# teensyMotors02_up_LED.net
KiCad netlist of a schematic drawn in EAGLE
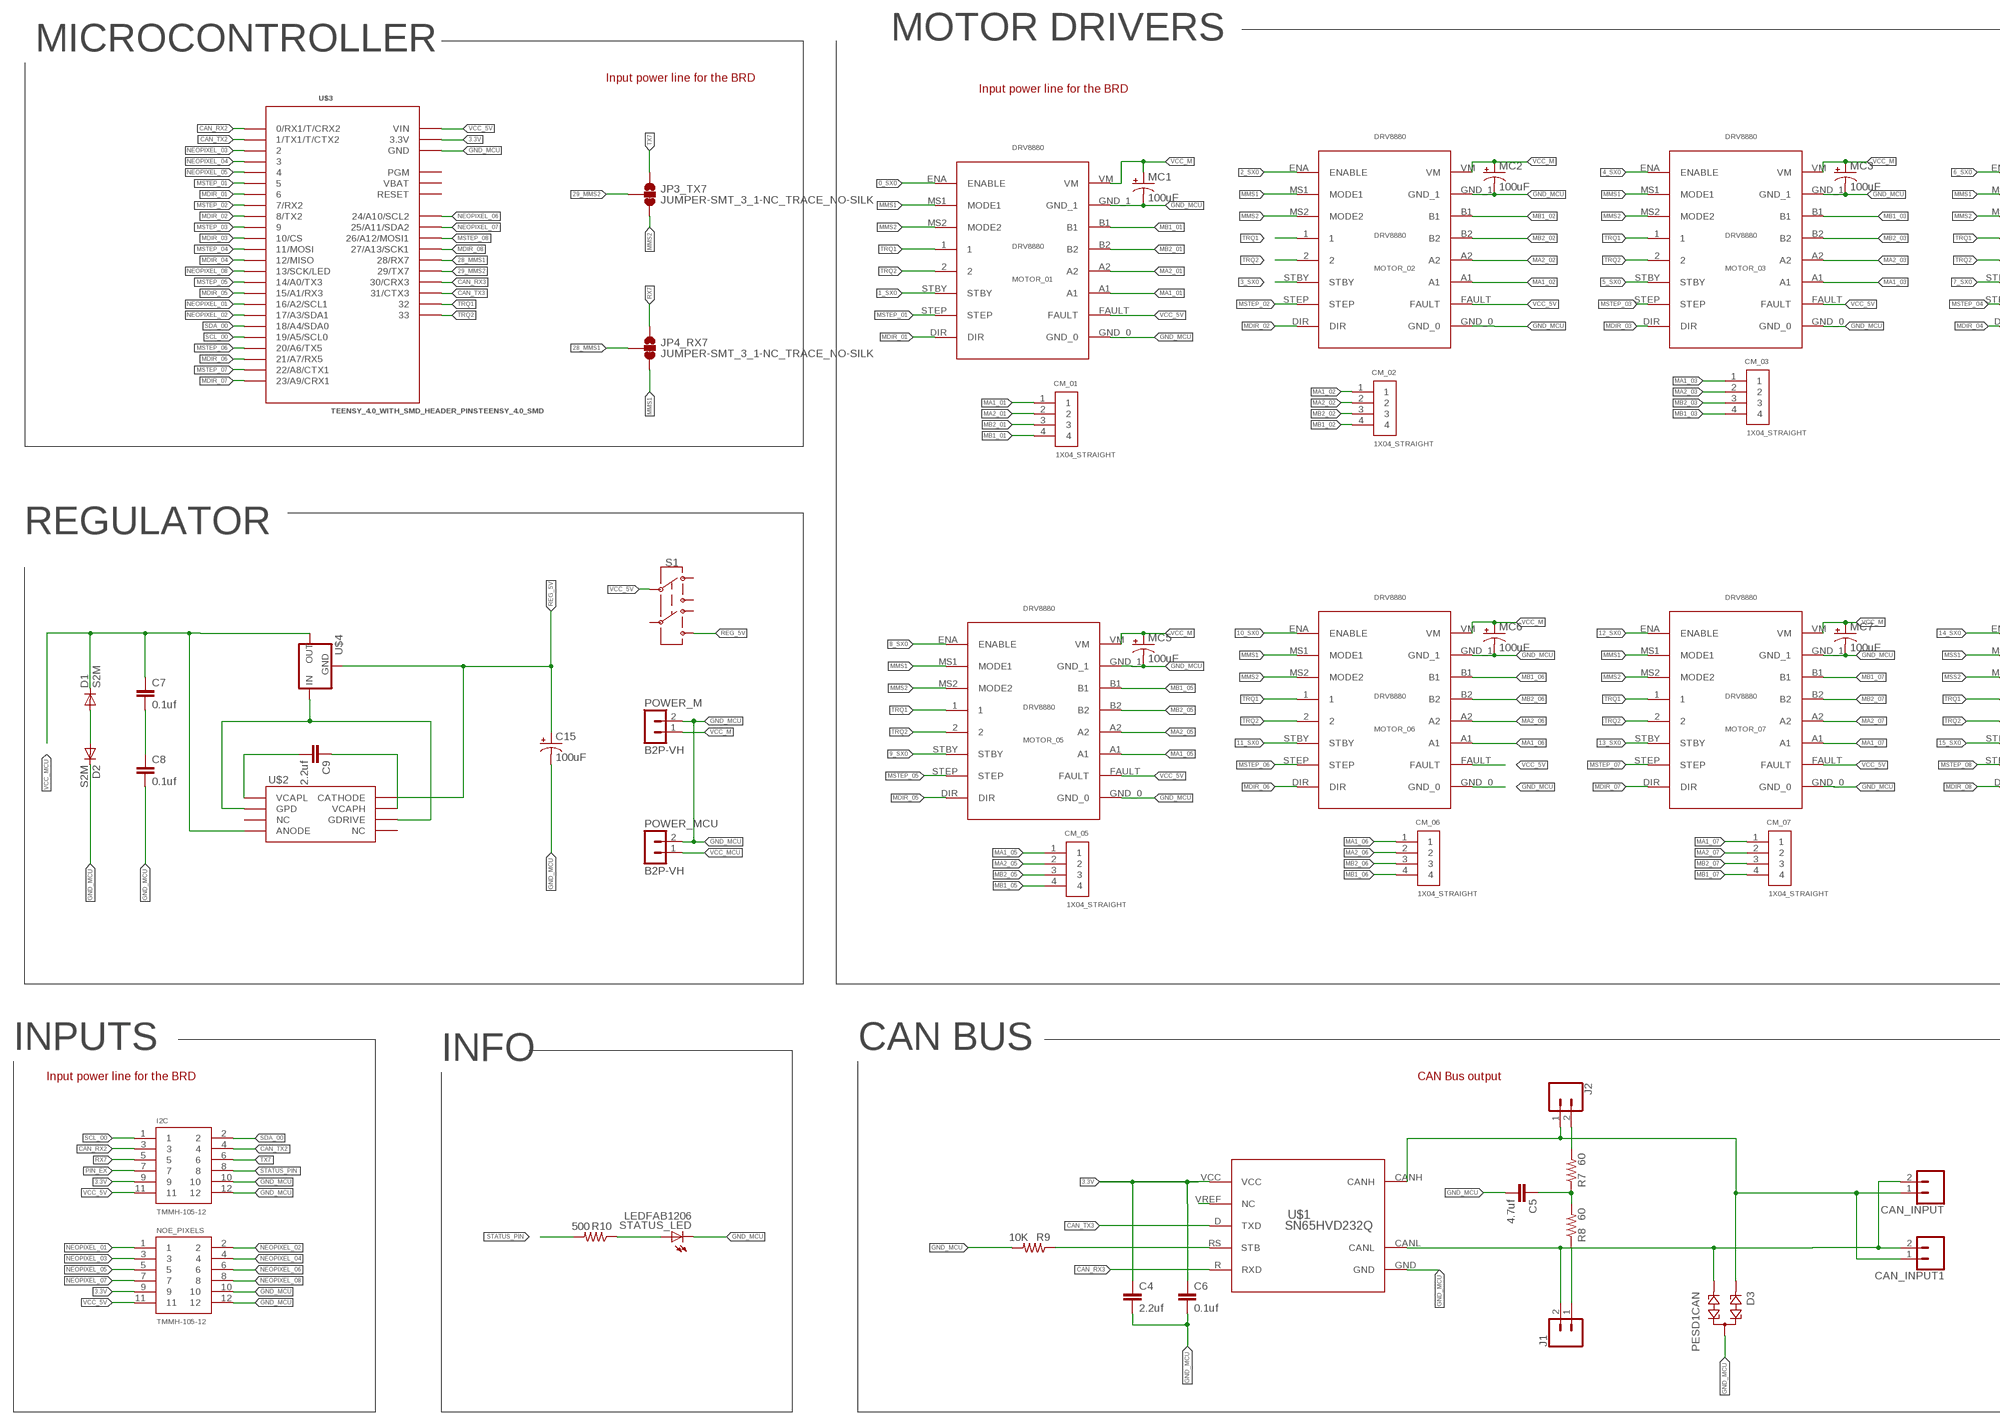
[diagram p0: schematic, sheet 1, part 1 of 2]
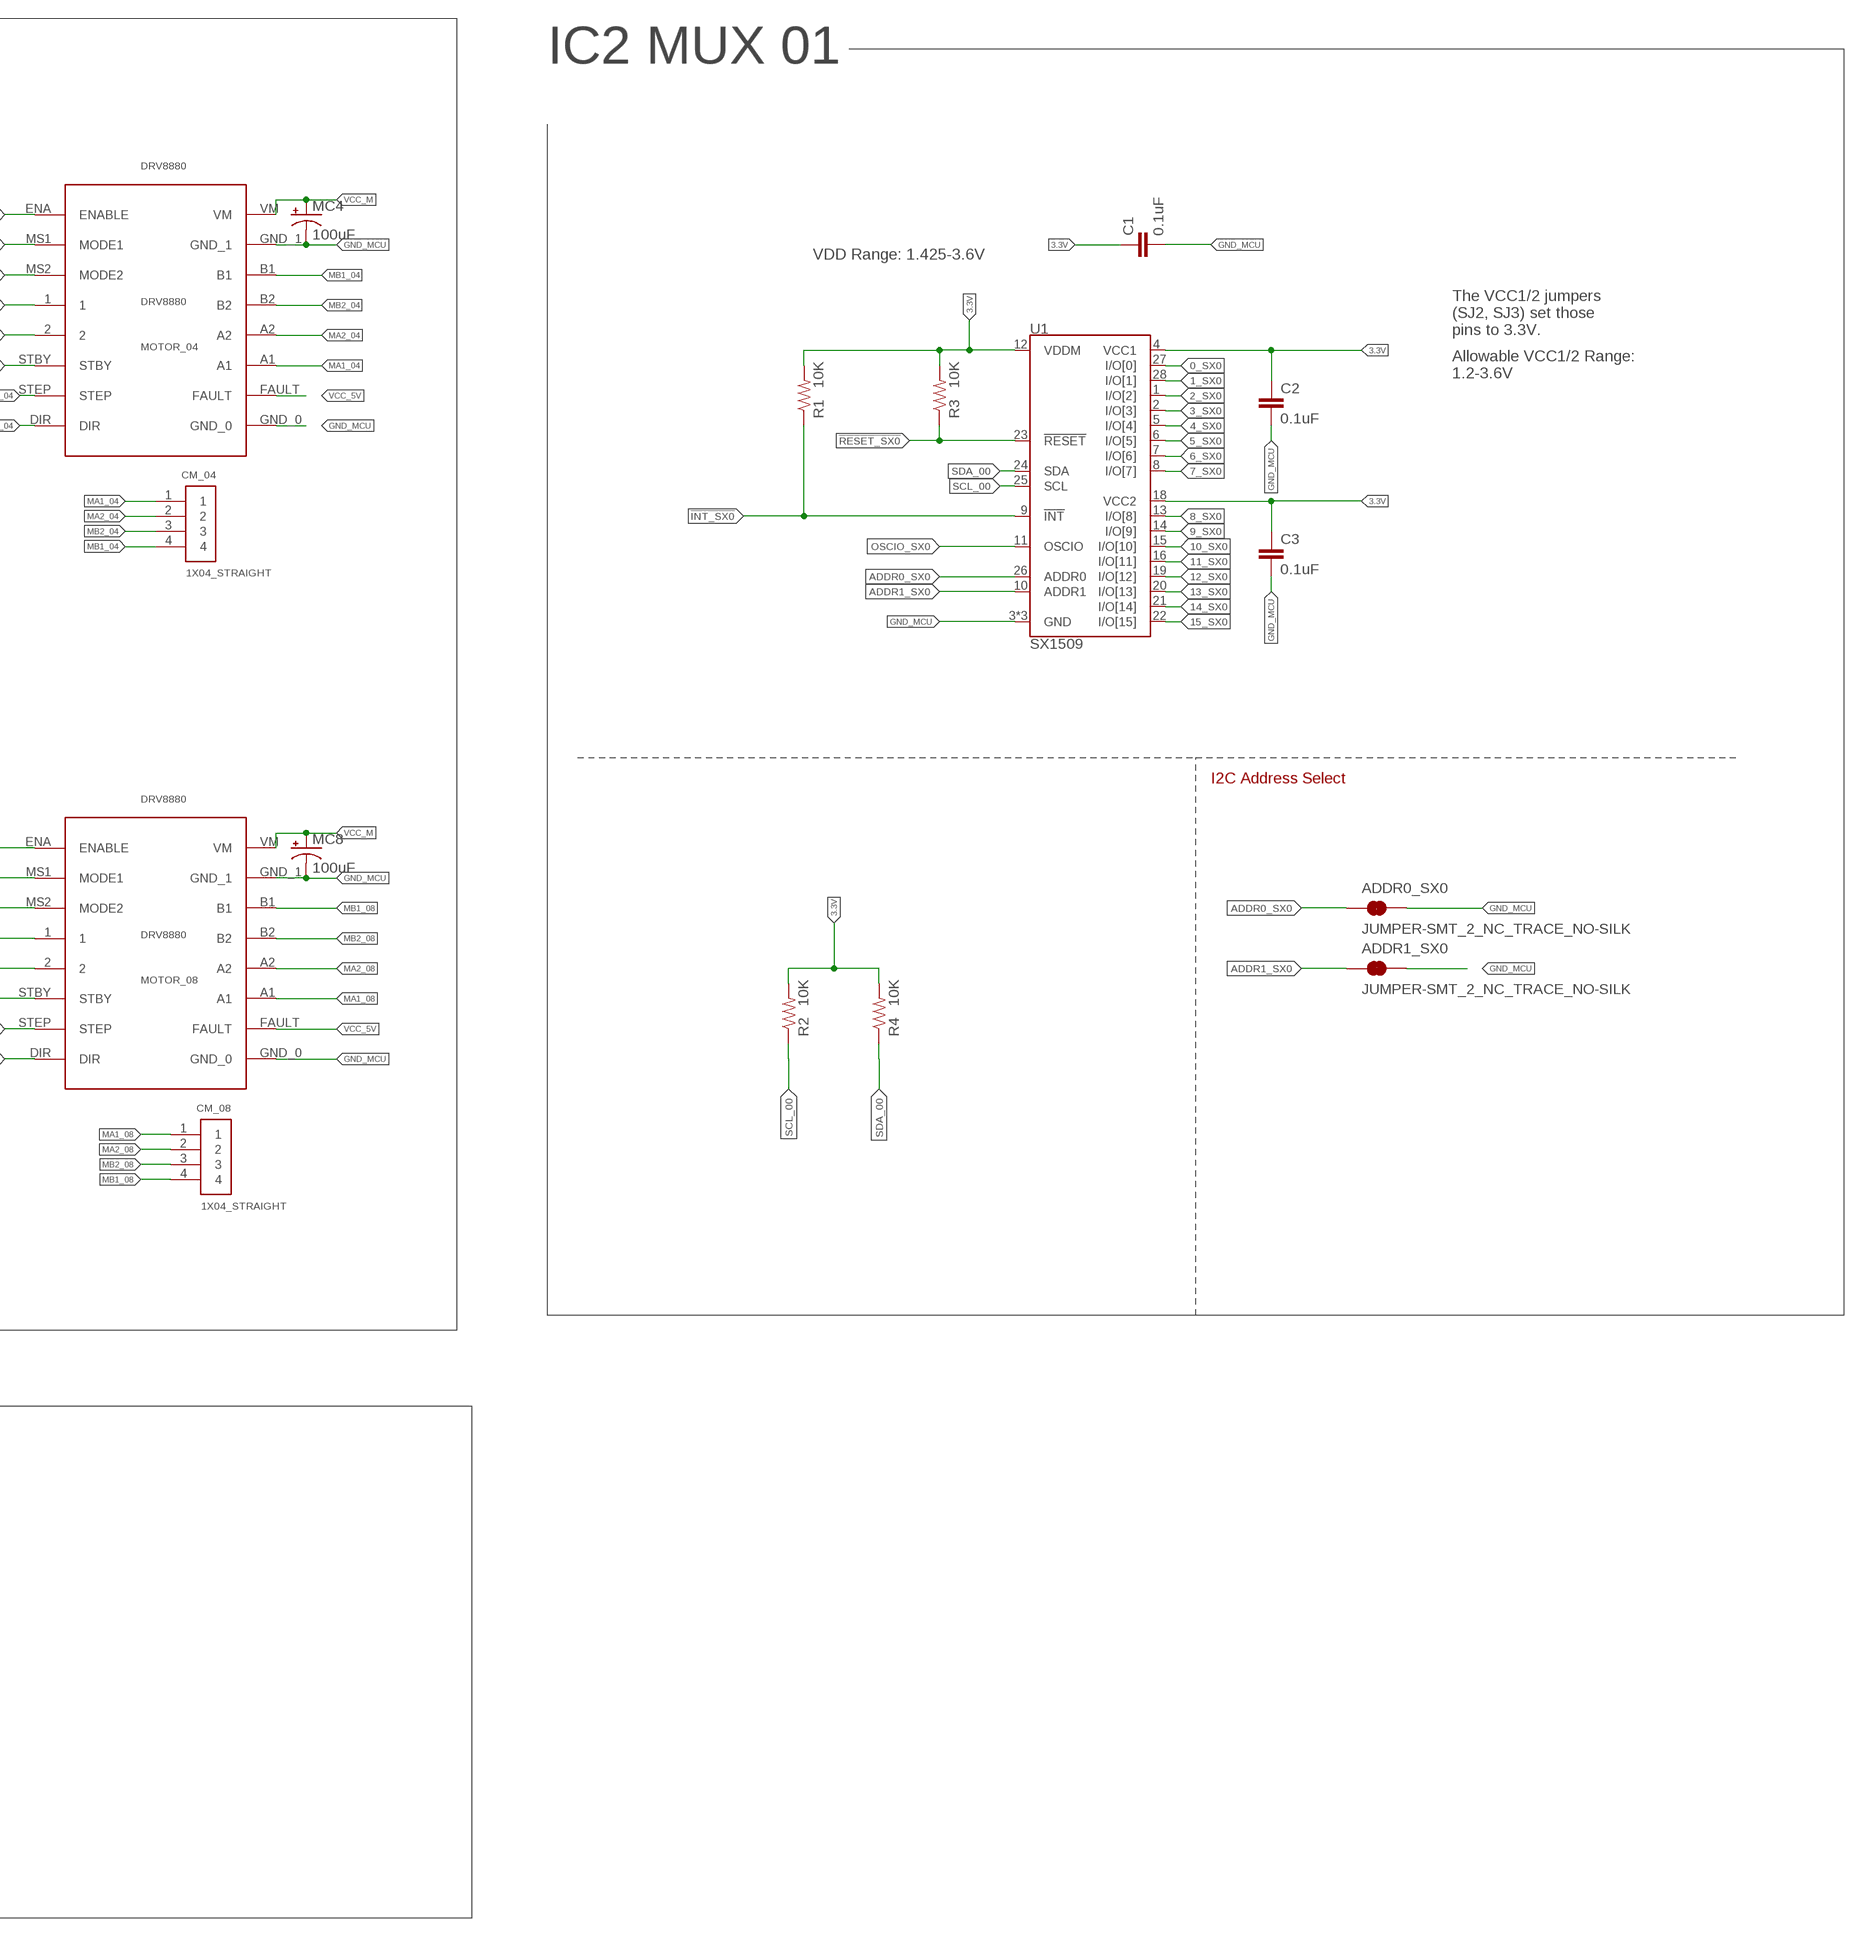
[diagram p1: schematic, sheet 1, part 2 of 2]

(export (version "E")
  (design (tool "Eeschema 10.0.6"))
  (components
    (comp (ref "ADDR0_SX0")
      (value "JUMPER-SMT_2_NC_TRACE_NO-SILK")
      (footprint "eagle-import:SMT-JUMPER_2_NC_TRACE_NO-SILK")
      (libsource (lib "eagle-import") (part "JUMPER-SMT_2_NC_TRACE_NO-SILK"))
    )
    (comp (ref "ADDR1_SX0")
      (value "JUMPER-SMT_2_NC_TRACE_NO-SILK")
      (footprint "eagle-import:SMT-JUMPER_2_NC_TRACE_NO-SILK")
      (libsource (lib "eagle-import") (part "JUMPER-SMT_2_NC_TRACE_NO-SILK"))
    )
    (comp (ref "C1")
      (value "0.1uF")
      (footprint "eagle-import:0603-CAP")
      (libsource (lib "eagle-import") (part "0.1UF-25V(+80/-20%)(0603)"))
    )
    (comp (ref "C2")
      (value "0.1uF")
      (footprint "eagle-import:0603-CAP")
      (libsource (lib "eagle-import") (part "0.1UF-25V(+80/-20%)(0603)"))
    )
    (comp (ref "C3")
      (value "0.1uF")
      (footprint "eagle-import:0603-CAP")
      (libsource (lib "eagle-import") (part "0.1UF-25V(+80/-20%)(0603)"))
    )
    (comp (ref "C4")
      (value "2.2uf")
      (footprint "eagle-import:0603-CAP")
      (libsource (lib "eagle-import") (part "0.1UF-25V(+80/-20%)(0603)"))
    )
    (comp (ref "C5")
      (value "4.7uf")
      (footprint "eagle-import:0603-CAP")
      (libsource (lib "eagle-import") (part "0.1UF-25V(+80/-20%)(0603)"))
    )
    (comp (ref "C6")
      (value "0.1uf")
      (footprint "eagle-import:0603-CAP")
      (libsource (lib "eagle-import") (part "0.1UF-25V(+80/-20%)(0603)"))
    )
    (comp (ref "C7")
      (value "0.1uf")
      (footprint "eagle-import:0603-CAP")
      (libsource (lib "eagle-import") (part "0.1UF-25V(+80/-20%)(0603)"))
    )
    (comp (ref "C8")
      (value "0.1uf")
      (footprint "eagle-import:0603-CAP")
      (libsource (lib "eagle-import") (part "0.1UF-25V(+80/-20%)(0603)"))
    )
    (comp (ref "C9")
      (value "2.2uf")
      (footprint "eagle-import:0603-CAP")
      (libsource (lib "eagle-import") (part "0.1UF-25V(+80/-20%)(0603)"))
    )
    (comp (ref "C15")
      (value "100uF")
      (footprint "eagle-import:PANASONIC_D")
      (libsource (lib "eagle-import") (part "100UF-POLAR-25V-20%(ELEC)"))
    )
    (comp (ref "CAN_INPUT")
      (value "CONN_02-JST-2MM-SMT")
      (footprint "eagle-import:JST-2-SMD")
      (libsource (lib "eagle-import") (part "CONN_02-JST-2MM-SMT"))
    )
    (comp (ref "CAN_INPUT1")
      (value "CONN_02-JST-2MM-SMT")
      (footprint "eagle-import:JST-2-SMD")
      (libsource (lib "eagle-import") (part "CONN_02-JST-2MM-SMT"))
    )
    (comp (ref "CM_01")
      (value "1X04_STRAIGHT")
      (footprint "eagle-import:1X04-CLEANBIG")
      (libsource (lib "eagle-import") (part "1X4-CLEANBIG"))
    )
    (comp (ref "CM_02")
      (value "1X04_STRAIGHT")
      (footprint "eagle-import:1X04-CLEANBIG")
      (libsource (lib "eagle-import") (part "1X4-CLEANBIG"))
    )
    (comp (ref "CM_03")
      (value "1X04_STRAIGHT")
      (footprint "eagle-import:1X04-CLEANBIG")
      (libsource (lib "eagle-import") (part "1X4-CLEANBIG"))
    )
    (comp (ref "CM_04")
      (value "1X04_STRAIGHT")
      (footprint "eagle-import:1X04-CLEANBIG")
      (libsource (lib "eagle-import") (part "1X4-CLEANBIG"))
    )
    (comp (ref "CM_05")
      (value "1X04_STRAIGHT")
      (footprint "eagle-import:1X04-CLEANBIG")
      (libsource (lib "eagle-import") (part "1X4-CLEANBIG"))
    )
    (comp (ref "CM_06")
      (value "1X04_STRAIGHT")
      (footprint "eagle-import:1X04-CLEANBIG")
      (libsource (lib "eagle-import") (part "1X4-CLEANBIG"))
    )
    (comp (ref "CM_07")
      (value "1X04_STRAIGHT")
      (footprint "eagle-import:1X04-CLEANBIG")
      (libsource (lib "eagle-import") (part "1X4-CLEANBIG"))
    )
    (comp (ref "CM_08")
      (value "1X04_STRAIGHT")
      (footprint "eagle-import:1X04-CLEANBIG")
      (libsource (lib "eagle-import") (part "1X4-CLEANBIG"))
    )
    (comp (ref "D1")
      (value "S2M")
      (footprint "eagle-import:DO214AA")
      (fields (field (name "MF") "Fairchild"))
      (libsource (lib "eagle-import") (part "S2M"))
    )
    (comp (ref "D2")
      (value "S2M")
      (footprint "eagle-import:DO214AA")
      (fields (field (name "MF") "Fairchild"))
      (libsource (lib "eagle-import") (part "S2M"))
    )
    (comp (ref "D3")
      (value "PESD1CAN")
      (footprint "eagle-import:SOT23")
      (libsource (lib "eagle-import") (part "PESD1CAN"))
    )
    (comp (ref "I2C")
      (value "TMMH-105-12")
      (footprint "eagle-import:TMMH-105-12")
      (libsource (lib "eagle-import") (part "TMMH-105-12"))
    )
    (comp (ref "J1")
      (value "CONN_02")
      (footprint "eagle-import:1X02")
      (libsource (lib "eagle-import") (part "CONN_02"))
    )
    (comp (ref "J2")
      (value "CONN_02")
      (footprint "eagle-import:1X02")
      (libsource (lib "eagle-import") (part "CONN_02"))
    )
    (comp (ref "JP3_TX7")
      (value "JUMPER-SMT_3_1-NC_TRACE_NO-SILK")
      (footprint "eagle-import:SMT-JUMPER_3_1-NC_TRACE_NO-SILK")
      (libsource (lib "eagle-import") (part "JUMPER-SMT_3_1-NC_TRACE_NO-SILK"))
    )
    (comp (ref "JP4_RX7")
      (value "JUMPER-SMT_3_1-NC_TRACE_NO-SILK")
      (footprint "eagle-import:SMT-JUMPER_3_1-NC_TRACE_NO-SILK")
      (libsource (lib "eagle-import") (part "JUMPER-SMT_3_1-NC_TRACE_NO-SILK"))
    )
    (comp (ref "MC1")
      (value "100uF")
      (footprint "eagle-import:PANASONIC_D")
      (libsource (lib "eagle-import") (part "100UF-POLAR-25V-20%(ELEC)"))
    )
    (comp (ref "MC2")
      (value "100uF")
      (footprint "eagle-import:PANASONIC_D")
      (libsource (lib "eagle-import") (part "100UF-POLAR-25V-20%(ELEC)"))
    )
    (comp (ref "MC3")
      (value "100uF")
      (footprint "eagle-import:PANASONIC_D")
      (libsource (lib "eagle-import") (part "100UF-POLAR-25V-20%(ELEC)"))
    )
    (comp (ref "MC4")
      (value "100uF")
      (footprint "eagle-import:PANASONIC_D")
      (libsource (lib "eagle-import") (part "100UF-POLAR-25V-20%(ELEC)"))
    )
    (comp (ref "MC5")
      (value "100uF")
      (footprint "eagle-import:PANASONIC_D")
      (libsource (lib "eagle-import") (part "100UF-POLAR-25V-20%(ELEC)"))
    )
    (comp (ref "MC6")
      (value "100uF")
      (footprint "eagle-import:PANASONIC_D")
      (libsource (lib "eagle-import") (part "100UF-POLAR-25V-20%(ELEC)"))
    )
    (comp (ref "MC7")
      (value "100uF")
      (footprint "eagle-import:PANASONIC_D")
      (libsource (lib "eagle-import") (part "100UF-POLAR-25V-20%(ELEC)"))
    )
    (comp (ref "MC8")
      (value "100uF")
      (footprint "eagle-import:PANASONIC_D")
      (libsource (lib "eagle-import") (part "100UF-POLAR-25V-20%(ELEC)"))
    )
    (comp (ref "MOTOR_01")
      (value "DRV8880")
      (footprint "eagle-import:DRV8880")
      (libsource (lib "eagle-import") (part "DRV8880"))
    )
    (comp (ref "MOTOR_02")
      (value "DRV8880")
      (footprint "eagle-import:DRV8880")
      (libsource (lib "eagle-import") (part "DRV8880"))
    )
    (comp (ref "MOTOR_03")
      (value "DRV8880")
      (footprint "eagle-import:DRV8880")
      (libsource (lib "eagle-import") (part "DRV8880"))
    )
    (comp (ref "MOTOR_04")
      (value "DRV8880")
      (footprint "eagle-import:DRV8880")
      (libsource (lib "eagle-import") (part "DRV8880"))
    )
    (comp (ref "MOTOR_05")
      (value "DRV8880")
      (footprint "eagle-import:DRV8880")
      (libsource (lib "eagle-import") (part "DRV8880"))
    )
    (comp (ref "MOTOR_06")
      (value "DRV8880")
      (footprint "eagle-import:DRV8880")
      (libsource (lib "eagle-import") (part "DRV8880"))
    )
    (comp (ref "MOTOR_07")
      (value "DRV8880")
      (footprint "eagle-import:DRV8880")
      (libsource (lib "eagle-import") (part "DRV8880"))
    )
    (comp (ref "MOTOR_08")
      (value "DRV8880")
      (footprint "eagle-import:DRV8880")
      (libsource (lib "eagle-import") (part "DRV8880"))
    )
    (comp (ref "NOE_PIXELS")
      (value "TMMH-105-12")
      (footprint "eagle-import:TMMH-105-12")
      (libsource (lib "eagle-import") (part "TMMH-105-12"))
    )
    (comp (ref "POWER_M")
      (value "B2P-VH")
      (footprint "eagle-import:B2P-VH")
      (libsource (lib "eagle-import") (part "B2P-VH"))
    )
    (comp (ref "POWER_MCU")
      (value "B2P-VH")
      (footprint "eagle-import:B2P-VH")
      (libsource (lib "eagle-import") (part "B2P-VH"))
    )
    (comp (ref "R1")
      (value "10K")
      (footprint "eagle-import:0603-RES")
      (libsource (lib "eagle-import") (part "10KOHM-1/10W-1%(0603)0603"))
    )
    (comp (ref "R2")
      (value "10K")
      (footprint "eagle-import:0603-RES")
      (libsource (lib "eagle-import") (part "10KOHM-1/10W-1%(0603)0603"))
    )
    (comp (ref "R3")
      (value "10K")
      (footprint "eagle-import:0603-RES")
      (libsource (lib "eagle-import") (part "10KOHM-1/10W-1%(0603)0603"))
    )
    (comp (ref "R4")
      (value "10K")
      (footprint "eagle-import:0603-RES")
      (libsource (lib "eagle-import") (part "10KOHM-1/10W-1%(0603)0603"))
    )
    (comp (ref "R7")
      (value "60")
      (footprint "eagle-import:0603-RES")
      (libsource (lib "eagle-import") (part "10KOHM-1/10W-1%(0603)0603"))
    )
    (comp (ref "R8")
      (value "60")
      (footprint "eagle-import:0603-RES")
      (libsource (lib "eagle-import") (part "10KOHM-1/10W-1%(0603)0603"))
    )
    (comp (ref "R9")
      (value "10K")
      (footprint "eagle-import:0603-RES")
      (libsource (lib "eagle-import") (part "10KOHM-1/10W-1%(0603)0603"))
    )
    (comp (ref "R10")
      (value "500")
      (footprint "eagle-import:0603-RES")
      (libsource (lib "eagle-import") (part "10KOHM-1/10W-1%(0603)0603"))
    )
    (comp (ref "S1")
      (value "SWITCH-DPDT-SMD-AYZ0202")
      (footprint "eagle-import:SWITCH_DPDT_SMD_AYZ0202")
      (fields (field (name "SPICEPREFIX") "X"))
      (libsource (lib "eagle-import") (part "SWITCH-DPDT-SMD-AYZ0202"))
    )
    (comp (ref "STATUS_LED")
      (value "LEDFAB1206")
      (footprint "eagle-import:LED1206FAB")
      (libsource (lib "eagle-import") (part "LEDFAB1206"))
    )
    (comp (ref "U$1")
      (value "SN65HVD232Q")
      (footprint "eagle-import:SN65HVD232Q")
      (libsource (lib "eagle-import") (part "SN65HVD232Q"))
    )
    (comp (ref "U$2")
      (value "LM74610-Q1")
      (footprint "eagle-import:VSSOP(8)")
      (fields (field (name "MPN") "LM74610-Q1 "))
      (libsource (lib "eagle-import") (part "LM74610-Q1"))
    )
    (comp (ref "U$3")
      (value "TEENSY_4.0_WITH_SMD_HEADER_PINSTEENSY_4.0_SMD")
      (footprint "eagle-import:TEENSY_4.0_SMD")
      (libsource (lib "eagle-import") (part "TEENSY_4.0_WITH_SMD_HEADER_PINSTEENSY_4.0_SMD"))
    )
    (comp (ref "U$4")
      (value "BUK")
      (footprint "eagle-import:TO263-3")
      (libsource (lib "eagle-import") (part "BUK"))
    )
    (comp (ref "U1")
      (value "SX1509")
      (footprint "eagle-import:QFN-28")
      (libsource (lib "eagle-import") (part "SX1509"))
    )
  )
  (nets
    (net (code "1") (name "0_SX0") (class "Default")
      (node (ref "MOTOR_01") (pin "ENA") (pinfunction "ENABLE_ENA") (pintype "bidirectional"))
      (node (ref "U1") (pin "27") (pinfunction "I/O[0]_27") (pintype "bidirectional"))
    )
    (net (code "2") (name "1_SX0") (class "Default")
      (node (ref "MOTOR_01") (pin "STBY") (pinfunction "STBY_STBY") (pintype "bidirectional"))
      (node (ref "U1") (pin "28") (pinfunction "I/O[1]_28") (pintype "bidirectional"))
    )
    (net (code "3") (name "2_SX0") (class "Default")
      (node (ref "MOTOR_02") (pin "ENA") (pinfunction "ENABLE_ENA") (pintype "bidirectional"))
      (node (ref "U1") (pin "1") (pinfunction "I/O[2]_1") (pintype "bidirectional"))
    )
    (net (code "4") (name "3.3V") (class "Default")
      (node (ref "C1") (pin "1") (pinfunction "1_1") (pintype "passive"))
      (node (ref "C2") (pin "1") (pinfunction "1_1") (pintype "passive"))
      (node (ref "C3") (pin "1") (pinfunction "1_1") (pintype "passive"))
      (node (ref "C4") (pin "1") (pinfunction "1_1") (pintype "passive"))
      (node (ref "C6") (pin "1") (pinfunction "1_1") (pintype "passive"))
      (node (ref "I2C") (pin "9") (pinfunction "9_9") (pintype "bidirectional"))
      (node (ref "NOE_PIXELS") (pin "9") (pinfunction "9_9") (pintype "bidirectional"))
      (node (ref "R1") (pin "2") (pinfunction "2_2") (pintype "passive"))
      (node (ref "R2") (pin "2") (pinfunction "2_2") (pintype "passive"))
      (node (ref "R3") (pin "2") (pinfunction "2_2") (pintype "passive"))
      (node (ref "R4") (pin "2") (pinfunction "2_2") (pintype "passive"))
      (node (ref "U$1") (pin "VCC") (pinfunction "VCC_VCC") (pintype "power_in"))
      (node (ref "U$3") (pin "3.3V") (pinfunction "3.3V_3.3V") (pintype "power_in"))
      (node (ref "U$3") (pin "3.3V1") (pinfunction "3.3V_3.3V1") (pintype "power_in"))
      (node (ref "U1") (pin "12") (pinfunction "VDDM_12") (pintype "bidirectional"))
      (node (ref "U1") (pin "18") (pinfunction "VCC2_18") (pintype "bidirectional"))
      (node (ref "U1") (pin "4") (pinfunction "VCC1_4") (pintype "bidirectional"))
    )
    (net (code "5") (name "3_SX0") (class "Default")
      (node (ref "MOTOR_02") (pin "STBY") (pinfunction "STBY_STBY") (pintype "bidirectional"))
      (node (ref "U1") (pin "2") (pinfunction "I/O[3]_2") (pintype "bidirectional"))
    )
    (net (code "6") (name "4_SX0") (class "Default")
      (node (ref "MOTOR_03") (pin "ENA") (pinfunction "ENABLE_ENA") (pintype "bidirectional"))
      (node (ref "U1") (pin "5") (pinfunction "I/O[4]_5") (pintype "bidirectional"))
    )
    (net (code "7") (name "5_SX0") (class "Default")
      (node (ref "MOTOR_03") (pin "STBY") (pinfunction "STBY_STBY") (pintype "bidirectional"))
      (node (ref "U1") (pin "6") (pinfunction "I/O[5]_6") (pintype "bidirectional"))
    )
    (net (code "8") (name "6_SX0") (class "Default")
      (node (ref "MOTOR_04") (pin "ENA") (pinfunction "ENABLE_ENA") (pintype "bidirectional"))
      (node (ref "U1") (pin "7") (pinfunction "I/O[6]_7") (pintype "bidirectional"))
    )
    (net (code "9") (name "7_SX0") (class "Default")
      (node (ref "MOTOR_04") (pin "STBY") (pinfunction "STBY_STBY") (pintype "bidirectional"))
      (node (ref "U1") (pin "8") (pinfunction "I/O[7]_8") (pintype "bidirectional"))
    )
    (net (code "10") (name "8_SX0") (class "Default")
      (node (ref "MOTOR_05") (pin "ENA") (pinfunction "ENABLE_ENA") (pintype "bidirectional"))
      (node (ref "U1") (pin "13") (pinfunction "I/O[8]_13") (pintype "bidirectional"))
    )
    (net (code "11") (name "9_SX0") (class "Default")
      (node (ref "MOTOR_05") (pin "STBY") (pinfunction "STBY_STBY") (pintype "bidirectional"))
      (node (ref "U1") (pin "14") (pinfunction "I/O[9]_14") (pintype "bidirectional"))
    )
    (net (code "12") (name "10_SX0") (class "Default")
      (node (ref "MOTOR_06") (pin "ENA") (pinfunction "ENABLE_ENA") (pintype "bidirectional"))
      (node (ref "U1") (pin "15") (pinfunction "I/O[10]_15") (pintype "bidirectional"))
    )
    (net (code "13") (name "11_SX0") (class "Default")
      (node (ref "MOTOR_06") (pin "STBY") (pinfunction "STBY_STBY") (pintype "bidirectional"))
      (node (ref "U1") (pin "16") (pinfunction "I/O[11]_16") (pintype "bidirectional"))
    )
    (net (code "14") (name "12_SX0") (class "Default")
      (node (ref "MOTOR_07") (pin "ENA") (pinfunction "ENABLE_ENA") (pintype "bidirectional"))
      (node (ref "U1") (pin "19") (pinfunction "I/O[12]_19") (pintype "bidirectional"))
    )
    (net (code "15") (name "13_SX0") (class "Default")
      (node (ref "MOTOR_07") (pin "STBY") (pinfunction "STBY_STBY") (pintype "bidirectional"))
      (node (ref "U1") (pin "20") (pinfunction "I/O[13]_20") (pintype "bidirectional"))
    )
    (net (code "16") (name "14_SX0") (class "Default")
      (node (ref "MOTOR_08") (pin "ENA") (pinfunction "ENABLE_ENA") (pintype "bidirectional"))
      (node (ref "U1") (pin "21") (pinfunction "I/O[14]_21") (pintype "bidirectional"))
    )
    (net (code "17") (name "15_SX0") (class "Default")
      (node (ref "MOTOR_08") (pin "STBY") (pinfunction "STBY_STBY") (pintype "bidirectional"))
      (node (ref "U1") (pin "22") (pinfunction "I/O[15]_22") (pintype "bidirectional"))
    )
    (net (code "18") (name "28_MMS1") (class "Default")
      (node (ref "JP4_RX7") (pin "2") (pinfunction "2_2") (pintype "passive"))
      (node (ref "U$3") (pin "28") (pinfunction "28/RX7_28") (pintype "bidirectional"))
    )
    (net (code "19") (name "29_MMS2") (class "Default")
      (node (ref "JP3_TX7") (pin "2") (pinfunction "2_2") (pintype "passive"))
      (node (ref "U$3") (pin "29") (pinfunction "29/TX7_29") (pintype "bidirectional"))
    )
    (net (code "20") (name "ADDR0_SX0") (class "Default")
      (node (ref "ADDR0_SX0") (pin "1") (pinfunction "1_1") (pintype "passive"))
      (node (ref "U1") (pin "26") (pinfunction "ADDR0_26") (pintype "bidirectional"))
    )
    (net (code "21") (name "ADDR1_SX0") (class "Default")
      (node (ref "ADDR1_SX0") (pin "1") (pinfunction "1_1") (pintype "passive"))
      (node (ref "U1") (pin "10") (pinfunction "ADDR1_10") (pintype "bidirectional"))
    )
    (net (code "22") (name "CAN_RX2") (class "Default")
      (node (ref "I2C") (pin "3") (pinfunction "3_3") (pintype "bidirectional"))
      (node (ref "U$3") (pin "0") (pinfunction "0/RX1/T/CRX2_0") (pintype "bidirectional"))
    )
    (net (code "23") (name "CAN_RX3") (class "Default")
      (node (ref "U$1") (pin "R") (pinfunction "RXD_R") (pintype "output"))
      (node (ref "U$3") (pin "30") (pinfunction "30/CRX3_30") (pintype "bidirectional"))
    )
    (net (code "24") (name "CAN_TX2") (class "Default")
      (node (ref "I2C") (pin "4") (pinfunction "4_4") (pintype "bidirectional"))
      (node (ref "U$3") (pin "1") (pinfunction "1/TX1/T/CTX2_1") (pintype "bidirectional"))
    )
    (net (code "25") (name "CAN_TX3") (class "Default")
      (node (ref "U$1") (pin "D") (pinfunction "TXD_D") (pintype "input"))
      (node (ref "U$3") (pin "31") (pinfunction "31/CTX3_31") (pintype "bidirectional"))
    )
    (net (code "26") (name "GND_MCU") (class "Default")
      (node (ref "ADDR0_SX0") (pin "2") (pinfunction "2_2") (pintype "passive"))
      (node (ref "ADDR1_SX0") (pin "2") (pinfunction "2_2") (pintype "passive"))
      (node (ref "C1") (pin "2") (pinfunction "2_2") (pintype "passive"))
      (node (ref "C15") (pin "-") (pinfunction "-_-") (pintype "passive"))
      (node (ref "C2") (pin "2") (pinfunction "2_2") (pintype "passive"))
      (node (ref "C3") (pin "2") (pinfunction "2_2") (pintype "passive"))
      (node (ref "C4") (pin "2") (pinfunction "2_2") (pintype "passive"))
      (node (ref "C5") (pin "2") (pinfunction "2_2") (pintype "passive"))
      (node (ref "C6") (pin "2") (pinfunction "2_2") (pintype "passive"))
      (node (ref "C8") (pin "2") (pinfunction "2_2") (pintype "passive"))
      (node (ref "D2") (pin "C") (pinfunction "C_C") (pintype "passive"))
      (node (ref "D3") (pin "3") (pinfunction "3_3") (pintype "passive"))
      (node (ref "I2C") (pin "10") (pinfunction "10_10") (pintype "bidirectional"))
      (node (ref "I2C") (pin "12") (pinfunction "12_12") (pintype "bidirectional"))
      (node (ref "MC1") (pin "-") (pinfunction "-_-") (pintype "passive"))
      (node (ref "MC2") (pin "-") (pinfunction "-_-") (pintype "passive"))
      (node (ref "MC3") (pin "-") (pinfunction "-_-") (pintype "passive"))
      (node (ref "MC4") (pin "-") (pinfunction "-_-") (pintype "passive"))
      (node (ref "MC5") (pin "-") (pinfunction "-_-") (pintype "passive"))
      (node (ref "MC6") (pin "-") (pinfunction "-_-") (pintype "passive"))
      (node (ref "MC7") (pin "-") (pinfunction "-_-") (pintype "passive"))
      (node (ref "MC8") (pin "-") (pinfunction "-_-") (pintype "passive"))
      (node (ref "MOTOR_01") (pin "GND_0") (pinfunction "GND_0_GND_0") (pintype "bidirectional"))
      (node (ref "MOTOR_01") (pin "GND_1") (pinfunction "GND_1_GND_1") (pintype "bidirectional"))
      (node (ref "MOTOR_02") (pin "GND_0") (pinfunction "GND_0_GND_0") (pintype "bidirectional"))
      (node (ref "MOTOR_02") (pin "GND_1") (pinfunction "GND_1_GND_1") (pintype "bidirectional"))
      (node (ref "MOTOR_03") (pin "GND_0") (pinfunction "GND_0_GND_0") (pintype "bidirectional"))
      (node (ref "MOTOR_03") (pin "GND_1") (pinfunction "GND_1_GND_1") (pintype "bidirectional"))
      (node (ref "MOTOR_04") (pin "GND_0") (pinfunction "GND_0_GND_0") (pintype "bidirectional"))
      (node (ref "MOTOR_04") (pin "GND_1") (pinfunction "GND_1_GND_1") (pintype "bidirectional"))
      (node (ref "MOTOR_05") (pin "GND_0") (pinfunction "GND_0_GND_0") (pintype "bidirectional"))
      (node (ref "MOTOR_05") (pin "GND_1") (pinfunction "GND_1_GND_1") (pintype "bidirectional"))
      (node (ref "MOTOR_06") (pin "GND_0") (pinfunction "GND_0_GND_0") (pintype "bidirectional"))
      (node (ref "MOTOR_06") (pin "GND_1") (pinfunction "GND_1_GND_1") (pintype "bidirectional"))
      (node (ref "MOTOR_07") (pin "GND_0") (pinfunction "GND_0_GND_0") (pintype "bidirectional"))
      (node (ref "MOTOR_07") (pin "GND_1") (pinfunction "GND_1_GND_1") (pintype "bidirectional"))
      (node (ref "MOTOR_08") (pin "GND_0") (pinfunction "GND_0_GND_0") (pintype "bidirectional"))
      (node (ref "MOTOR_08") (pin "GND_1") (pinfunction "GND_1_GND_1") (pintype "bidirectional"))
      (node (ref "NOE_PIXELS") (pin "10") (pinfunction "10_10") (pintype "bidirectional"))
      (node (ref "NOE_PIXELS") (pin "12") (pinfunction "12_12") (pintype "bidirectional"))
      (node (ref "POWER_M") (pin "2") (pinfunction "2_2") (pintype "passive"))
      (node (ref "POWER_MCU") (pin "2") (pinfunction "2_2") (pintype "passive"))
      (node (ref "R9") (pin "2") (pinfunction "2_2") (pintype "passive"))
      (node (ref "STATUS_LED") (pin "2") (pinfunction "C_2") (pintype "passive"))
      (node (ref "U$1") (pin "GND") (pinfunction "GND_GND") (pintype "power_in"))
      (node (ref "U$3") (pin "GND") (pinfunction "GND_GND") (pintype "power_in"))
      (node (ref "U$3") (pin "GND1") (pinfunction "GND_GND1") (pintype "power_in"))
      (node (ref "U$3") (pin "GND2") (pinfunction "GND_GND2") (pintype "power_in"))
      (node (ref "U1") (pin "17") (pinfunction "GND_17") (pintype "bidirectional"))
      (node (ref "U1") (pin "29") (pinfunction "GND_29") (pintype "bidirectional"))
      (node (ref "U1") (pin "3") (pinfunction "GND_3") (pintype "bidirectional"))
    )
    (net (code "27") (name "MA1_01") (class "Default")
      (node (ref "CM_01") (pin "1") (pinfunction "1_1") (pintype "bidirectional"))
      (node (ref "MOTOR_01") (pin "A1") (pinfunction "A1_A1") (pintype "bidirectional"))
    )
    (net (code "28") (name "MA1_02") (class "Default")
      (node (ref "CM_02") (pin "1") (pinfunction "1_1") (pintype "bidirectional"))
      (node (ref "MOTOR_02") (pin "A1") (pinfunction "A1_A1") (pintype "bidirectional"))
    )
    (net (code "29") (name "MA1_03") (class "Default")
      (node (ref "CM_03") (pin "1") (pinfunction "1_1") (pintype "bidirectional"))
      (node (ref "MOTOR_03") (pin "A1") (pinfunction "A1_A1") (pintype "bidirectional"))
    )
    (net (code "30") (name "MA1_04") (class "Default")
      (node (ref "CM_04") (pin "1") (pinfunction "1_1") (pintype "bidirectional"))
      (node (ref "MOTOR_04") (pin "A1") (pinfunction "A1_A1") (pintype "bidirectional"))
    )
    (net (code "31") (name "MA1_05") (class "Default")
      (node (ref "CM_05") (pin "1") (pinfunction "1_1") (pintype "bidirectional"))
      (node (ref "MOTOR_05") (pin "A1") (pinfunction "A1_A1") (pintype "bidirectional"))
    )
    (net (code "32") (name "MA1_06") (class "Default")
      (node (ref "CM_06") (pin "1") (pinfunction "1_1") (pintype "bidirectional"))
      (node (ref "MOTOR_06") (pin "A1") (pinfunction "A1_A1") (pintype "bidirectional"))
    )
    (net (code "33") (name "MA1_07") (class "Default")
      (node (ref "CM_07") (pin "1") (pinfunction "1_1") (pintype "bidirectional"))
      (node (ref "MOTOR_07") (pin "A1") (pinfunction "A1_A1") (pintype "bidirectional"))
    )
    (net (code "34") (name "MA1_08") (class "Default")
      (node (ref "CM_08") (pin "1") (pinfunction "1_1") (pintype "bidirectional"))
      (node (ref "MOTOR_08") (pin "A1") (pinfunction "A1_A1") (pintype "bidirectional"))
    )
    (net (code "35") (name "MA2_01") (class "Default")
      (node (ref "CM_01") (pin "2") (pinfunction "2_2") (pintype "bidirectional"))
      (node (ref "MOTOR_01") (pin "A2") (pinfunction "A2_A2") (pintype "bidirectional"))
    )
    (net (code "36") (name "MA2_02") (class "Default")
      (node (ref "CM_02") (pin "2") (pinfunction "2_2") (pintype "bidirectional"))
      (node (ref "MOTOR_02") (pin "A2") (pinfunction "A2_A2") (pintype "bidirectional"))
    )
    (net (code "37") (name "MA2_03") (class "Default")
      (node (ref "CM_03") (pin "2") (pinfunction "2_2") (pintype "bidirectional"))
      (node (ref "MOTOR_03") (pin "A2") (pinfunction "A2_A2") (pintype "bidirectional"))
    )
    (net (code "38") (name "MA2_04") (class "Default")
      (node (ref "CM_04") (pin "2") (pinfunction "2_2") (pintype "bidirectional"))
      (node (ref "MOTOR_04") (pin "A2") (pinfunction "A2_A2") (pintype "bidirectional"))
    )
    (net (code "39") (name "MA2_05") (class "Default")
      (node (ref "CM_05") (pin "2") (pinfunction "2_2") (pintype "bidirectional"))
      (node (ref "MOTOR_05") (pin "A2") (pinfunction "A2_A2") (pintype "bidirectional"))
    )
    (net (code "40") (name "MA2_06") (class "Default")
      (node (ref "CM_06") (pin "2") (pinfunction "2_2") (pintype "bidirectional"))
      (node (ref "MOTOR_06") (pin "A2") (pinfunction "A2_A2") (pintype "bidirectional"))
    )
    (net (code "41") (name "MA2_07") (class "Default")
      (node (ref "CM_07") (pin "2") (pinfunction "2_2") (pintype "bidirectional"))
      (node (ref "MOTOR_07") (pin "A2") (pinfunction "A2_A2") (pintype "bidirectional"))
    )
    (net (code "42") (name "MA2_08") (class "Default")
      (node (ref "CM_08") (pin "2") (pinfunction "2_2") (pintype "bidirectional"))
      (node (ref "MOTOR_08") (pin "A2") (pinfunction "A2_A2") (pintype "bidirectional"))
    )
    (net (code "43") (name "MB1_01") (class "Default")
      (node (ref "CM_01") (pin "4") (pinfunction "4_4") (pintype "bidirectional"))
      (node (ref "MOTOR_01") (pin "B1") (pinfunction "B1_B1") (pintype "bidirectional"))
    )
    (net (code "44") (name "MB1_02") (class "Default")
      (node (ref "CM_02") (pin "4") (pinfunction "4_4") (pintype "bidirectional"))
      (node (ref "MOTOR_02") (pin "B1") (pinfunction "B1_B1") (pintype "bidirectional"))
    )
    (net (code "45") (name "MB1_03") (class "Default")
      (node (ref "CM_03") (pin "4") (pinfunction "4_4") (pintype "bidirectional"))
      (node (ref "MOTOR_03") (pin "B1") (pinfunction "B1_B1") (pintype "bidirectional"))
    )
    (net (code "46") (name "MB1_04") (class "Default")
      (node (ref "CM_04") (pin "4") (pinfunction "4_4") (pintype "bidirectional"))
      (node (ref "MOTOR_04") (pin "B1") (pinfunction "B1_B1") (pintype "bidirectional"))
    )
    (net (code "47") (name "MB1_05") (class "Default")
      (node (ref "CM_05") (pin "4") (pinfunction "4_4") (pintype "bidirectional"))
      (node (ref "MOTOR_05") (pin "B1") (pinfunction "B1_B1") (pintype "bidirectional"))
    )
    (net (code "48") (name "MB1_06") (class "Default")
      (node (ref "CM_06") (pin "4") (pinfunction "4_4") (pintype "bidirectional"))
      (node (ref "MOTOR_06") (pin "B1") (pinfunction "B1_B1") (pintype "bidirectional"))
    )
    (net (code "49") (name "MB1_07") (class "Default")
      (node (ref "CM_07") (pin "4") (pinfunction "4_4") (pintype "bidirectional"))
      (node (ref "MOTOR_07") (pin "B1") (pinfunction "B1_B1") (pintype "bidirectional"))
    )
    (net (code "50") (name "MB1_08") (class "Default")
      (node (ref "CM_08") (pin "4") (pinfunction "4_4") (pintype "bidirectional"))
      (node (ref "MOTOR_08") (pin "B1") (pinfunction "B1_B1") (pintype "bidirectional"))
    )
    (net (code "51") (name "MB2_01") (class "Default")
      (node (ref "CM_01") (pin "3") (pinfunction "3_3") (pintype "bidirectional"))
      (node (ref "MOTOR_01") (pin "B2") (pinfunction "B2_B2") (pintype "bidirectional"))
    )
    (net (code "52") (name "MB2_02") (class "Default")
      (node (ref "CM_02") (pin "3") (pinfunction "3_3") (pintype "bidirectional"))
      (node (ref "MOTOR_02") (pin "B2") (pinfunction "B2_B2") (pintype "bidirectional"))
    )
    (net (code "53") (name "MB2_03") (class "Default")
      (node (ref "CM_03") (pin "3") (pinfunction "3_3") (pintype "bidirectional"))
      (node (ref "MOTOR_03") (pin "B2") (pinfunction "B2_B2") (pintype "bidirectional"))
    )
    (net (code "54") (name "MB2_04") (class "Default")
      (node (ref "CM_04") (pin "3") (pinfunction "3_3") (pintype "bidirectional"))
      (node (ref "MOTOR_04") (pin "B2") (pinfunction "B2_B2") (pintype "bidirectional"))
    )
    (net (code "55") (name "MB2_05") (class "Default")
      (node (ref "CM_05") (pin "3") (pinfunction "3_3") (pintype "bidirectional"))
      (node (ref "MOTOR_05") (pin "B2") (pinfunction "B2_B2") (pintype "bidirectional"))
    )
    (net (code "56") (name "MB2_06") (class "Default")
      (node (ref "CM_06") (pin "3") (pinfunction "3_3") (pintype "bidirectional"))
      (node (ref "MOTOR_06") (pin "B2") (pinfunction "B2_B2") (pintype "bidirectional"))
    )
    (net (code "57") (name "MB2_07") (class "Default")
      (node (ref "CM_07") (pin "3") (pinfunction "3_3") (pintype "bidirectional"))
      (node (ref "MOTOR_07") (pin "B2") (pinfunction "B2_B2") (pintype "bidirectional"))
    )
    (net (code "58") (name "MB2_08") (class "Default")
      (node (ref "CM_08") (pin "3") (pinfunction "3_3") (pintype "bidirectional"))
      (node (ref "MOTOR_08") (pin "B2") (pinfunction "B2_B2") (pintype "bidirectional"))
    )
    (net (code "59") (name "MDIR_01") (class "Default")
      (node (ref "MOTOR_01") (pin "DIR") (pinfunction "DIR_DIR") (pintype "bidirectional"))
      (node (ref "U$3") (pin "6") (pinfunction "6_6") (pintype "bidirectional"))
    )
    (net (code "60") (name "MDIR_02") (class "Default")
      (node (ref "MOTOR_02") (pin "DIR") (pinfunction "DIR_DIR") (pintype "bidirectional"))
      (node (ref "U$3") (pin "8") (pinfunction "8/TX2_8") (pintype "bidirectional"))
    )
    (net (code "61") (name "MDIR_03") (class "Default")
      (node (ref "MOTOR_03") (pin "DIR") (pinfunction "DIR_DIR") (pintype "bidirectional"))
      (node (ref "U$3") (pin "10") (pinfunction "10/CS_10") (pintype "bidirectional"))
    )
    (net (code "62") (name "MDIR_04") (class "Default")
      (node (ref "MOTOR_04") (pin "DIR") (pinfunction "DIR_DIR") (pintype "bidirectional"))
      (node (ref "U$3") (pin "12") (pinfunction "12/MISO_12") (pintype "bidirectional"))
    )
    (net (code "63") (name "MDIR_05") (class "Default")
      (node (ref "MOTOR_05") (pin "DIR") (pinfunction "DIR_DIR") (pintype "bidirectional"))
      (node (ref "U$3") (pin "15/A1") (pinfunction "15/A1/RX3_15/A1") (pintype "bidirectional"))
    )
    (net (code "64") (name "MDIR_06") (class "Default")
      (node (ref "MOTOR_06") (pin "DIR") (pinfunction "DIR_DIR") (pintype "bidirectional"))
      (node (ref "U$3") (pin "21/A7") (pinfunction "21/A7/RX5_21/A7") (pintype "bidirectional"))
    )
    (net (code "65") (name "MDIR_07") (class "Default")
      (node (ref "MOTOR_07") (pin "DIR") (pinfunction "DIR_DIR") (pintype "bidirectional"))
      (node (ref "U$3") (pin "23/A9") (pinfunction "23/A9/CRX1_23/A9") (pintype "bidirectional"))
    )
    (net (code "66") (name "MDIR_08") (class "Default")
      (node (ref "MOTOR_08") (pin "DIR") (pinfunction "DIR_DIR") (pintype "bidirectional"))
      (node (ref "U$3") (pin "27") (pinfunction "27/A13/SCK1_27") (pintype "bidirectional"))
    )
    (net (code "67") (name "MMS1") (class "Default")
      (node (ref "JP4_RX7") (pin "3") (pinfunction "3_3") (pintype "passive"))
      (node (ref "MOTOR_01") (pin "MS1") (pinfunction "MODE1_MS1") (pintype "bidirectional"))
      (node (ref "MOTOR_02") (pin "MS1") (pinfunction "MODE1_MS1") (pintype "bidirectional"))
      (node (ref "MOTOR_03") (pin "MS1") (pinfunction "MODE1_MS1") (pintype "bidirectional"))
      (node (ref "MOTOR_04") (pin "MS1") (pinfunction "MODE1_MS1") (pintype "bidirectional"))
      (node (ref "MOTOR_05") (pin "MS1") (pinfunction "MODE1_MS1") (pintype "bidirectional"))
      (node (ref "MOTOR_06") (pin "MS1") (pinfunction "MODE1_MS1") (pintype "bidirectional"))
      (node (ref "MOTOR_07") (pin "MS1") (pinfunction "MODE1_MS1") (pintype "bidirectional"))
    )
    (net (code "68") (name "MMS2") (class "Default")
      (node (ref "JP3_TX7") (pin "3") (pinfunction "3_3") (pintype "passive"))
      (node (ref "MOTOR_01") (pin "MS2") (pinfunction "MODE2_MS2") (pintype "bidirectional"))
      (node (ref "MOTOR_02") (pin "MS2") (pinfunction "MODE2_MS2") (pintype "bidirectional"))
      (node (ref "MOTOR_03") (pin "MS2") (pinfunction "MODE2_MS2") (pintype "bidirectional"))
      (node (ref "MOTOR_04") (pin "MS2") (pinfunction "MODE2_MS2") (pintype "bidirectional"))
      (node (ref "MOTOR_05") (pin "MS2") (pinfunction "MODE2_MS2") (pintype "bidirectional"))
      (node (ref "MOTOR_06") (pin "MS2") (pinfunction "MODE2_MS2") (pintype "bidirectional"))
      (node (ref "MOTOR_07") (pin "MS2") (pinfunction "MODE2_MS2") (pintype "bidirectional"))
    )
    (net (code "69") (name "MSS1") (class "Default")
      (node (ref "MOTOR_08") (pin "MS1") (pinfunction "MODE1_MS1") (pintype "bidirectional"))
    )
    (net (code "70") (name "MSS2") (class "Default")
      (node (ref "MOTOR_08") (pin "MS2") (pinfunction "MODE2_MS2") (pintype "bidirectional"))
    )
    (net (code "71") (name "MSTEP_01") (class "Default")
      (node (ref "MOTOR_01") (pin "STEP") (pinfunction "STEP_STEP") (pintype "bidirectional"))
      (node (ref "U$3") (pin "5") (pinfunction "5_5") (pintype "bidirectional"))
    )
    (net (code "72") (name "MSTEP_02") (class "Default")
      (node (ref "MOTOR_02") (pin "STEP") (pinfunction "STEP_STEP") (pintype "bidirectional"))
      (node (ref "U$3") (pin "7") (pinfunction "7/RX2_7") (pintype "bidirectional"))
    )
    (net (code "73") (name "MSTEP_03") (class "Default")
      (node (ref "MOTOR_03") (pin "STEP") (pinfunction "STEP_STEP") (pintype "bidirectional"))
      (node (ref "U$3") (pin "9") (pinfunction "9_9") (pintype "bidirectional"))
    )
    (net (code "74") (name "MSTEP_04") (class "Default")
      (node (ref "MOTOR_04") (pin "STEP") (pinfunction "STEP_STEP") (pintype "bidirectional"))
      (node (ref "U$3") (pin "11") (pinfunction "11/MOSI_11") (pintype "bidirectional"))
    )
    (net (code "75") (name "MSTEP_05") (class "Default")
      (node (ref "MOTOR_05") (pin "STEP") (pinfunction "STEP_STEP") (pintype "bidirectional"))
      (node (ref "U$3") (pin "14/A0") (pinfunction "14/A0/TX3_14/A0") (pintype "bidirectional"))
    )
    (net (code "76") (name "MSTEP_06") (class "Default")
      (node (ref "MOTOR_06") (pin "STEP") (pinfunction "STEP_STEP") (pintype "bidirectional"))
      (node (ref "U$3") (pin "20/A6") (pinfunction "20/A6/TX5_20/A6") (pintype "bidirectional"))
    )
    (net (code "77") (name "MSTEP_07") (class "Default")
      (node (ref "MOTOR_07") (pin "STEP") (pinfunction "STEP_STEP") (pintype "bidirectional"))
      (node (ref "U$3") (pin "22/A8") (pinfunction "22/A8/CTX1_22/A8") (pintype "bidirectional"))
    )
    (net (code "78") (name "MSTEP_08") (class "Default")
      (node (ref "MOTOR_08") (pin "STEP") (pinfunction "STEP_STEP") (pintype "bidirectional"))
      (node (ref "U$3") (pin "26") (pinfunction "26/A12/MOSI1_26") (pintype "bidirectional"))
    )
    (net (code "79") (name "NEOPIXEL_01") (class "Default")
      (node (ref "NOE_PIXELS") (pin "1") (pinfunction "1_1") (pintype "bidirectional"))
      (node (ref "U$3") (pin "16/A2") (pinfunction "16/A2/SCL1_16/A2") (pintype "bidirectional"))
    )
    (net (code "80") (name "NEOPIXEL_02") (class "Default")
      (node (ref "NOE_PIXELS") (pin "2") (pinfunction "2_2") (pintype "bidirectional"))
      (node (ref "U$3") (pin "17/A3") (pinfunction "17/A3/SDA1_17/A3") (pintype "bidirectional"))
    )
    (net (code "81") (name "NEOPIXEL_03") (class "Default")
      (node (ref "NOE_PIXELS") (pin "3") (pinfunction "3_3") (pintype "bidirectional"))
      (node (ref "U$3") (pin "2") (pinfunction "2_2") (pintype "bidirectional"))
    )
    (net (code "82") (name "NEOPIXEL_04") (class "Default")
      (node (ref "NOE_PIXELS") (pin "4") (pinfunction "4_4") (pintype "bidirectional"))
      (node (ref "U$3") (pin "3") (pinfunction "3_3") (pintype "bidirectional"))
    )
    (net (code "83") (name "NEOPIXEL_05") (class "Default")
      (node (ref "NOE_PIXELS") (pin "5") (pinfunction "5_5") (pintype "bidirectional"))
      (node (ref "U$3") (pin "4") (pinfunction "4_4") (pintype "bidirectional"))
    )
    (net (code "84") (name "NEOPIXEL_06") (class "Default")
      (node (ref "NOE_PIXELS") (pin "6") (pinfunction "6_6") (pintype "bidirectional"))
      (node (ref "U$3") (pin "24") (pinfunction "24/A10/SCL2_24") (pintype "bidirectional"))
    )
    (net (code "85") (name "NEOPIXEL_07") (class "Default")
      (node (ref "NOE_PIXELS") (pin "7") (pinfunction "7_7") (pintype "bidirectional"))
      (node (ref "U$3") (pin "25") (pinfunction "25/A11/SDA2_25") (pintype "bidirectional"))
    )
    (net (code "86") (name "NEOPIXEL_08") (class "Default")
      (node (ref "NOE_PIXELS") (pin "8") (pinfunction "8_8") (pintype "bidirectional"))
      (node (ref "U$3") (pin "13") (pinfunction "13/SCK/LED_13") (pintype "bidirectional"))
    )
    (net (code "87") (name "Net-(C5-Pad1)") (class "Default")
      (node (ref "C5") (pin "1") (pinfunction "1_1") (pintype "passive"))
      (node (ref "R7") (pin "1") (pinfunction "1_1") (pintype "passive"))
      (node (ref "R8") (pin "2") (pinfunction "2_2") (pintype "passive"))
    )
    (net (code "88") (name "Net-(C7-Pad2)") (class "Default")
      (node (ref "C7") (pin "2") (pinfunction "2_2") (pintype "passive"))
      (node (ref "C8") (pin "1") (pinfunction "1_1") (pintype "passive"))
    )
    (net (code "89") (name "Net-(C9-Pad1)") (class "Default")
      (node (ref "C9") (pin "1") (pinfunction "1_1") (pintype "passive"))
      (node (ref "U$2") (pin "VCAPH") (pinfunction "VCAPH_VCAPH") (pintype "bidirectional"))
    )
    (net (code "90") (name "Net-(C9-Pad2)") (class "Default")
      (node (ref "C9") (pin "2") (pinfunction "2_2") (pintype "passive"))
      (node (ref "U$2") (pin "VCAPL") (pinfunction "VCAPL_VCAPL") (pintype "bidirectional"))
    )
    (net (code "91") (name "Net-(CAN_INPUT-1)") (class "Default")
      (node (ref "CAN_INPUT") (pin "2") (pinfunction "1_2") (pintype "passive"))
      (node (ref "CAN_INPUT1") (pin "2") (pinfunction "1_2") (pintype "passive"))
      (node (ref "D3") (pin "2") (pinfunction "2_2") (pintype "passive"))
      (node (ref "J1") (pin "2") (pinfunction "2_2") (pintype "passive"))
      (node (ref "U$1") (pin "CANL") (pinfunction "CANL_CANL") (pintype "bidirectional"))
    )
    (net (code "92") (name "Net-(CAN_INPUT-2)") (class "Default")
      (node (ref "CAN_INPUT") (pin "1") (pinfunction "2_1") (pintype "passive"))
      (node (ref "CAN_INPUT1") (pin "1") (pinfunction "2_1") (pintype "passive"))
      (node (ref "D3") (pin "1") (pinfunction "1_1") (pintype "passive"))
      (node (ref "J2") (pin "1") (pinfunction "1_1") (pintype "passive"))
      (node (ref "U$1") (pin "CANH") (pinfunction "CANH_CANH") (pintype "bidirectional"))
    )
    (net (code "93") (name "Net-(D1-PadA)") (class "Default")
      (node (ref "D1") (pin "A") (pinfunction "A_A") (pintype "passive"))
      (node (ref "D2") (pin "A") (pinfunction "A_A") (pintype "passive"))
    )
    (net (code "94") (name "Net-(J1-Pad1)") (class "Default")
      (node (ref "J1") (pin "1") (pinfunction "1_1") (pintype "passive"))
      (node (ref "R8") (pin "1") (pinfunction "1_1") (pintype "passive"))
    )
    (net (code "95") (name "Net-(J2-Pad2)") (class "Default")
      (node (ref "J2") (pin "2") (pinfunction "2_2") (pintype "passive"))
      (node (ref "R7") (pin "2") (pinfunction "2_2") (pintype "passive"))
    )
    (net (code "96") (name "Net-(STATUS_LED-A)") (class "Default")
      (node (ref "R10") (pin "1") (pinfunction "1_1") (pintype "passive"))
      (node (ref "STATUS_LED") (pin "1") (pinfunction "A_1") (pintype "passive"))
    )
    (net (code "97") (name "Net-(U$1-STB)") (class "Default")
      (node (ref "R9") (pin "1") (pinfunction "1_1") (pintype "passive"))
      (node (ref "U$1") (pin "RS") (pinfunction "STB_RS") (pintype "input"))
    )
    (net (code "98") (name "Net-(U$4-IN)") (class "Default")
      (node (ref "U$2") (pin "GDRIVE") (pinfunction "GDRIVE_GDRIVE") (pintype "bidirectional"))
      (node (ref "U$2") (pin "GPD") (pinfunction "GPD_GPD") (pintype "bidirectional"))
      (node (ref "U$4") (pin "1") (pinfunction "IN_1") (pintype "input"))
    )
    (net (code "99") (name "OSCIO_SX0") (class "Default")
      (node (ref "U1") (pin "11") (pinfunction "OSCIO_11") (pintype "bidirectional"))
    )
    (net (code "100") (name "PIN_EX") (class "Default")
      (node (ref "I2C") (pin "7") (pinfunction "7_7") (pintype "bidirectional"))
    )
    (net (code "101") (name "REG_5V") (class "Default")
      (node (ref "C15") (pin "+") (pinfunction "+_+") (pintype "passive"))
      (node (ref "S1") (pin "6") (pinfunction "6_6") (pintype "bidirectional"))
      (node (ref "U$2") (pin "CATHODE") (pinfunction "CATHODE_CATHODE") (pintype "bidirectional"))
      (node (ref "U$4") (pin "4") (pinfunction "GND_4") (pintype "input"))
    )
    (net (code "102") (name "RX7") (class "Default")
      (node (ref "I2C") (pin "5") (pinfunction "5_5") (pintype "bidirectional"))
      (node (ref "JP4_RX7") (pin "1") (pinfunction "1_1") (pintype "passive"))
    )
    (net (code "103") (name "SCL_00") (class "Default")
      (node (ref "I2C") (pin "1") (pinfunction "1_1") (pintype "bidirectional"))
      (node (ref "R2") (pin "1") (pinfunction "1_1") (pintype "passive"))
      (node (ref "U$3") (pin "19/A5") (pinfunction "19/A5/SCL0_19/A5") (pintype "bidirectional"))
      (node (ref "U1") (pin "25") (pinfunction "SCL_25") (pintype "bidirectional"))
    )
    (net (code "104") (name "SDA_00") (class "Default")
      (node (ref "I2C") (pin "2") (pinfunction "2_2") (pintype "bidirectional"))
      (node (ref "R4") (pin "1") (pinfunction "1_1") (pintype "passive"))
      (node (ref "U$3") (pin "18/A4") (pinfunction "18/A4/SDA0_18/A4") (pintype "bidirectional"))
      (node (ref "U1") (pin "24") (pinfunction "SDA_24") (pintype "bidirectional"))
    )
    (net (code "105") (name "STATUS_PIN") (class "Default")
      (node (ref "I2C") (pin "8") (pinfunction "8_8") (pintype "bidirectional"))
      (node (ref "R10") (pin "2") (pinfunction "2_2") (pintype "passive"))
    )
    (net (code "106") (name "TRQ1") (class "Default")
      (node (ref "MOTOR_01") (pin "1") (pinfunction "1_1") (pintype "bidirectional"))
      (node (ref "MOTOR_02") (pin "1") (pinfunction "1_1") (pintype "bidirectional"))
      (node (ref "MOTOR_03") (pin "1") (pinfunction "1_1") (pintype "bidirectional"))
      (node (ref "MOTOR_04") (pin "1") (pinfunction "1_1") (pintype "bidirectional"))
      (node (ref "MOTOR_05") (pin "1") (pinfunction "1_1") (pintype "bidirectional"))
      (node (ref "MOTOR_06") (pin "1") (pinfunction "1_1") (pintype "bidirectional"))
      (node (ref "MOTOR_07") (pin "1") (pinfunction "1_1") (pintype "bidirectional"))
      (node (ref "MOTOR_08") (pin "1") (pinfunction "1_1") (pintype "bidirectional"))
      (node (ref "U$3") (pin "32") (pinfunction "32_32") (pintype "bidirectional"))
    )
    (net (code "107") (name "TRQ2") (class "Default")
      (node (ref "MOTOR_01") (pin "2") (pinfunction "2_2") (pintype "bidirectional"))
      (node (ref "MOTOR_02") (pin "2") (pinfunction "2_2") (pintype "bidirectional"))
      (node (ref "MOTOR_03") (pin "2") (pinfunction "2_2") (pintype "bidirectional"))
      (node (ref "MOTOR_04") (pin "2") (pinfunction "2_2") (pintype "bidirectional"))
      (node (ref "MOTOR_05") (pin "2") (pinfunction "2_2") (pintype "bidirectional"))
      (node (ref "MOTOR_06") (pin "2") (pinfunction "2_2") (pintype "bidirectional"))
      (node (ref "MOTOR_07") (pin "2") (pinfunction "2_2") (pintype "bidirectional"))
      (node (ref "MOTOR_08") (pin "2") (pinfunction "2_2") (pintype "bidirectional"))
      (node (ref "U$3") (pin "33") (pinfunction "33_33") (pintype "bidirectional"))
    )
    (net (code "108") (name "TX7") (class "Default")
      (node (ref "I2C") (pin "6") (pinfunction "6_6") (pintype "bidirectional"))
      (node (ref "JP3_TX7") (pin "1") (pinfunction "1_1") (pintype "passive"))
    )
    (net (code "109") (name "VBAT") (class "Default")
      (node (ref "U$3") (pin "VBAT") (pinfunction "VBAT_VBAT") (pintype "power_in"))
    )
    (net (code "110") (name "VCC_5V") (class "Default")
      (node (ref "I2C") (pin "11") (pinfunction "11_11") (pintype "bidirectional"))
      (node (ref "MOTOR_01") (pin "FAULT") (pinfunction "FAULT_FAULT") (pintype "bidirectional"))
      (node (ref "MOTOR_02") (pin "FAULT") (pinfunction "FAULT_FAULT") (pintype "bidirectional"))
      (node (ref "MOTOR_03") (pin "FAULT") (pinfunction "FAULT_FAULT") (pintype "bidirectional"))
      (node (ref "MOTOR_04") (pin "FAULT") (pinfunction "FAULT_FAULT") (pintype "bidirectional"))
      (node (ref "MOTOR_05") (pin "FAULT") (pinfunction "FAULT_FAULT") (pintype "bidirectional"))
      (node (ref "MOTOR_06") (pin "FAULT") (pinfunction "FAULT_FAULT") (pintype "bidirectional"))
      (node (ref "MOTOR_07") (pin "FAULT") (pinfunction "FAULT_FAULT") (pintype "bidirectional"))
      (node (ref "MOTOR_08") (pin "FAULT") (pinfunction "FAULT_FAULT") (pintype "bidirectional"))
      (node (ref "NOE_PIXELS") (pin "11") (pinfunction "11_11") (pintype "bidirectional"))
      (node (ref "S1") (pin "2") (pinfunction "2_2") (pintype "bidirectional"))
      (node (ref "U$3") (pin "VIN") (pinfunction "VIN_VIN") (pintype "power_in"))
    )
    (net (code "111") (name "VCC_M") (class "Default")
      (node (ref "MC1") (pin "+") (pinfunction "+_+") (pintype "passive"))
      (node (ref "MC2") (pin "+") (pinfunction "+_+") (pintype "passive"))
      (node (ref "MC3") (pin "+") (pinfunction "+_+") (pintype "passive"))
      (node (ref "MC4") (pin "+") (pinfunction "+_+") (pintype "passive"))
      (node (ref "MC5") (pin "+") (pinfunction "+_+") (pintype "passive"))
      (node (ref "MC6") (pin "+") (pinfunction "+_+") (pintype "passive"))
      (node (ref "MC7") (pin "+") (pinfunction "+_+") (pintype "passive"))
      (node (ref "MC8") (pin "+") (pinfunction "+_+") (pintype "passive"))
      (node (ref "MOTOR_01") (pin "VM") (pinfunction "VM_VM") (pintype "bidirectional"))
      (node (ref "MOTOR_02") (pin "VM") (pinfunction "VM_VM") (pintype "bidirectional"))
      (node (ref "MOTOR_03") (pin "VM") (pinfunction "VM_VM") (pintype "bidirectional"))
      (node (ref "MOTOR_04") (pin "VM") (pinfunction "VM_VM") (pintype "bidirectional"))
      (node (ref "MOTOR_05") (pin "VM") (pinfunction "VM_VM") (pintype "bidirectional"))
      (node (ref "MOTOR_06") (pin "VM") (pinfunction "VM_VM") (pintype "bidirectional"))
      (node (ref "MOTOR_07") (pin "VM") (pinfunction "VM_VM") (pintype "bidirectional"))
      (node (ref "MOTOR_08") (pin "VM") (pinfunction "VM_VM") (pintype "bidirectional"))
      (node (ref "POWER_M") (pin "1") (pinfunction "1_1") (pintype "passive"))
    )
    (net (code "112") (name "VCC_MCU") (class "Default")
      (node (ref "C7") (pin "1") (pinfunction "1_1") (pintype "passive"))
      (node (ref "D1") (pin "C") (pinfunction "C_C") (pintype "passive"))
      (node (ref "POWER_MCU") (pin "1") (pinfunction "1_1") (pintype "passive"))
      (node (ref "U$2") (pin "ANODE") (pinfunction "ANODE_ANODE") (pintype "bidirectional"))
      (node (ref "U$4") (pin "3") (pinfunction "OUT_3") (pintype "passive"))
    )
    (net (code "113") (name "unconnected-(S1-Pad1)") (class "Default")
      (node (ref "S1") (pin "1") (pinfunction "1_1") (pintype "bidirectional"))
    )
    (net (code "114") (name "unconnected-(S1-Pad3)") (class "Default")
      (node (ref "S1") (pin "3") (pinfunction "3_3") (pintype "bidirectional"))
    )
    (net (code "115") (name "unconnected-(S1-Pad4)") (class "Default")
      (node (ref "S1") (pin "4") (pinfunction "4_4") (pintype "bidirectional"))
    )
    (net (code "116") (name "unconnected-(S1-Pad5)") (class "Default")
      (node (ref "S1") (pin "5") (pinfunction "5_5") (pintype "bidirectional"))
    )
    (net (code "117") (name "unconnected-(U$1-NC-PadVREF)") (class "Default")
      (node (ref "U$1") (pin "VREF") (pinfunction "NC_VREF") (pintype "passive"))
    )
    (net (code "118") (name "unconnected-(U$2-NC-PadNC@1)") (class "Default")
      (node (ref "U$2") (pin "NC@1") (pinfunction "NC_NC@1") (pintype "no_connect"))
    )
    (net (code "119") (name "unconnected-(U$2-NC-PadNC@2)") (class "Default")
      (node (ref "U$2") (pin "NC@2") (pinfunction "NC_NC@2") (pintype "no_connect"))
    )
    (net (code "120") (name "unconnected-(U$3-PadPGM)") (class "Default")
      (node (ref "U$3") (pin "PGM") (pinfunction "PGM_PGM") (pintype "bidirectional"))
    )
    (net (code "121") (name "unconnected-(U$3-PadRESET)") (class "Default")
      (node (ref "U$3") (pin "RESET") (pinfunction "RESET_RESET") (pintype "bidirectional"))
    )
    (net (code "122") (name "~{INT_SX0}") (class "Default")
      (node (ref "R1") (pin "1") (pinfunction "1_1") (pintype "passive"))
      (node (ref "U1") (pin "9") (pinfunction "~{INT}_9") (pintype "bidirectional"))
    )
    (net (code "123") (name "~{RESET_SX0}") (class "Default")
      (node (ref "R3") (pin "1") (pinfunction "1_1") (pintype "passive"))
      (node (ref "U1") (pin "23") (pinfunction "~{RESET}_23") (pintype "bidirectional"))
    )
  )
)
